# 08-DIPSwitches_I2C.net
KiCad netlist of a schematic drawn in Altium Designer
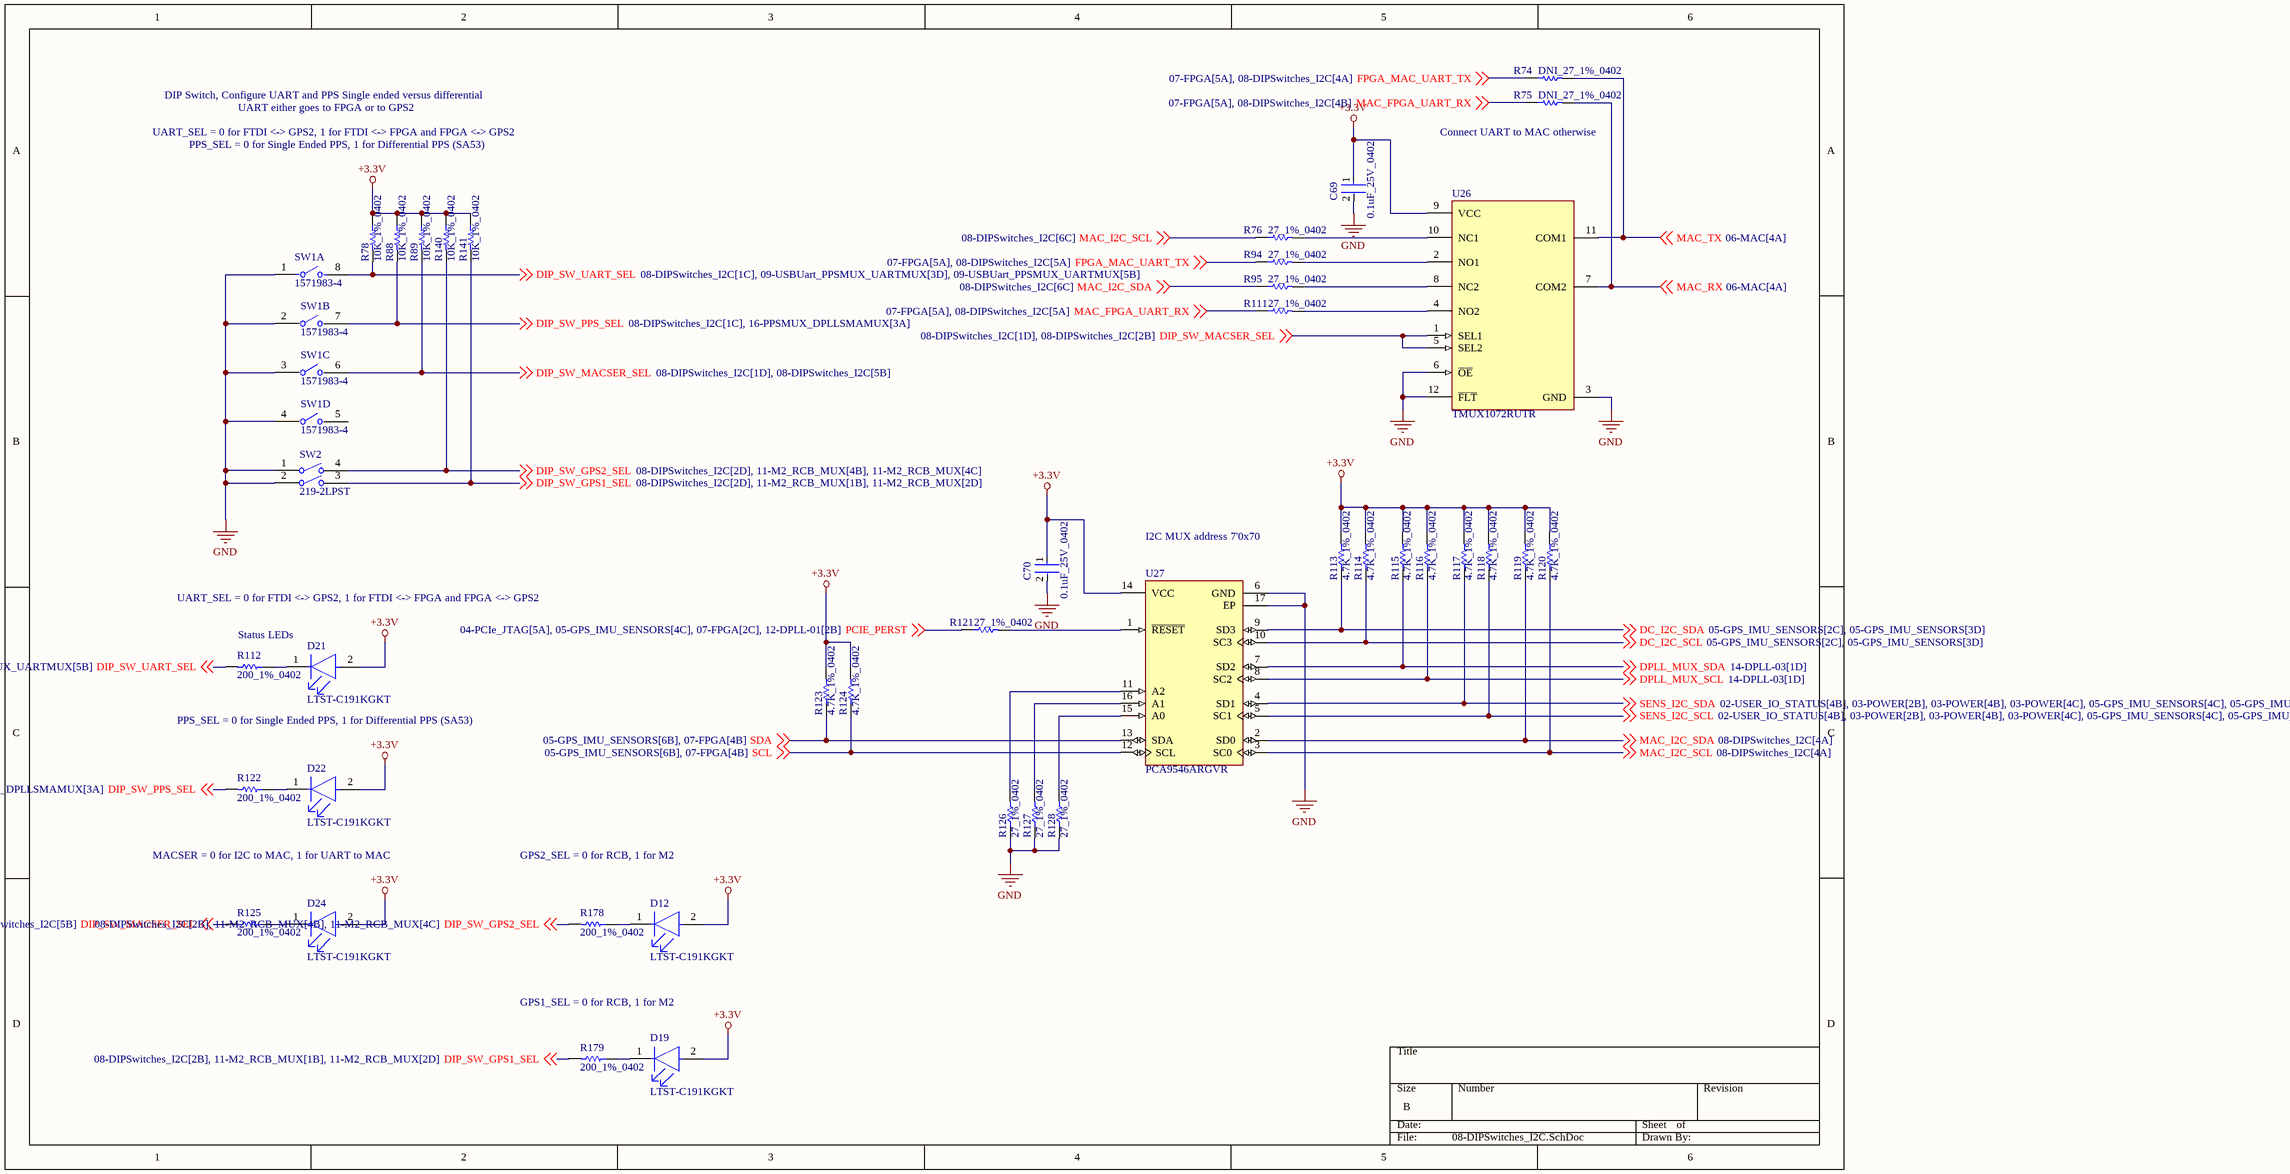
[diagram p0: 08-DIPSwitches_I2C.SchDoc]

(export (version "E")
  (design (tool "Eeschema 10.0.6"))
  (components
    (comp (ref "C69")
      (value "0.1uF_25V_0402")
      (footprint "FP-0402-L_1_0_1-W_0_5_0_1-IPC_C")
      (description "General Purpose Ceramic Capacitor, 0402, 100nF, 10%, X7R, 15%, 25V")
      (fields (field (name "VOLTAGE") "25V") (field (name "TOLERANCE") "10%"))
      (libsource (lib "Altium Content Vault") (part "b4654b650e69147ec39a6b967a45e02"))
    )
    (comp (ref "C70")
      (value "0.1uF_25V_0402")
      (footprint "FP-0402-L_1_0_1-W_0_5_0_1-IPC_C")
      (description "General Purpose Ceramic Capacitor, 0402, 100nF, 10%, X7R, 15%, 25V")
      (fields (field (name "VOLTAGE") "25V") (field (name "TOLERANCE") "10%"))
      (libsource (lib "Altium Content Vault") (part "b4654b650e69147ec39a6b967a45e02"))
    )
    (comp (ref "D12")
      (value "LTST-C191KGKT")
      (footprint "FP-LTST-C191KGKT-MFG")
      (description "LED GREEN CLEAR SMD")
      (libsource (lib "Altium Content Vault") (part "8706943c75ba83719d021d2fdc84c58"))
    )
    (comp (ref "D19")
      (value "LTST-C191KGKT")
      (footprint "FP-LTST-C191KGKT-MFG")
      (description "LED GREEN CLEAR SMD")
      (libsource (lib "Altium Content Vault") (part "8706943c75ba83719d021d2fdc84c58"))
    )
    (comp (ref "D21")
      (value "LTST-C191KGKT")
      (footprint "FP-LTST-C191KGKT-MFG")
      (description "LED GREEN CLEAR SMD")
      (libsource (lib "Altium Content Vault") (part "8706943c75ba83719d021d2fdc84c58"))
    )
    (comp (ref "D22")
      (value "LTST-C191KGKT")
      (footprint "FP-LTST-C191KGKT-MFG")
      (description "LED GREEN CLEAR SMD")
      (libsource (lib "Altium Content Vault") (part "8706943c75ba83719d021d2fdc84c58"))
    )
    (comp (ref "D24")
      (value "LTST-C191KGKT")
      (footprint "FP-LTST-C191KGKT-MFG")
      (description "LED GREEN CLEAR SMD")
      (libsource (lib "Altium Content Vault") (part "8706943c75ba83719d021d2fdc84c58"))
    )
    (comp (ref "R74")
      (value "DNI_27_1%_0402")
      (footprint "RESC1005X40X25NL05T05")
      (fields (field (name "PART NUMBER") "CRCW040227R0FKED") (field (name "MANUFACTURER") "Vishay Dale"))
      (libsource (lib "Altium Content Vault") (part "RES"))
    )
    (comp (ref "R75")
      (value "DNI_27_1%_0402")
      (footprint "RESC1005X40X25NL05T05")
      (fields (field (name "PART NUMBER") "CRCW040227R0FKED") (field (name "MANUFACTURER") "Vishay Dale"))
      (libsource (lib "Altium Content Vault") (part "RES"))
    )
    (comp (ref "R76")
      (value "27_1%_0402")
      (footprint "RESC1005X40X25NL05T05")
      (fields (field (name "PART NUMBER") "CRCW040227R0FKED") (field (name "MANUFACTURER") "Vishay Dale"))
      (libsource (lib "Altium Content Vault") (part "RES"))
    )
    (comp (ref "R78")
      (value "10K_1%_0402")
      (footprint "RESC1005X40X25LL05T10")
      (fields (field (name "PART NUMBER") "RC0402FR-0710KL") (field (name "MANUFACTURER") "Yageo / Phycomp"))
      (libsource (lib "Altium Content Vault") (part "RES"))
    )
    (comp (ref "R88")
      (value "10K_1%_0402")
      (footprint "RESC1005X40X25LL05T10")
      (fields (field (name "PART NUMBER") "RC0402FR-0710KL") (field (name "MANUFACTURER") "Yageo / Phycomp"))
      (libsource (lib "Altium Content Vault") (part "RES"))
    )
    (comp (ref "R89")
      (value "10K_1%_0402")
      (footprint "RESC1005X40X25LL05T10")
      (fields (field (name "PART NUMBER") "RC0402FR-0710KL") (field (name "MANUFACTURER") "Yageo / Phycomp"))
      (libsource (lib "Altium Content Vault") (part "RES"))
    )
    (comp (ref "R94")
      (value "27_1%_0402")
      (footprint "RESC1005X40X25NL05T05")
      (fields (field (name "PART NUMBER") "CRCW040227R0FKED") (field (name "MANUFACTURER") "Vishay Dale"))
      (libsource (lib "Altium Content Vault") (part "RES"))
    )
    (comp (ref "R95")
      (value "27_1%_0402")
      (footprint "RESC1005X40X25NL05T05")
      (fields (field (name "PART NUMBER") "CRCW040227R0FKED") (field (name "MANUFACTURER") "Vishay Dale"))
      (libsource (lib "Altium Content Vault") (part "RES"))
    )
    (comp (ref "R111")
      (value "27_1%_0402")
      (footprint "RESC1005X40X25NL05T05")
      (fields (field (name "PART NUMBER") "CRCW040227R0FKED") (field (name "MANUFACTURER") "Vishay Dale"))
      (libsource (lib "Altium Content Vault") (part "RES"))
    )
    (comp (ref "R112")
      (value "200_1%_0402")
      (footprint "RESC1005X40X25NL05T05")
      (fields (field (name "MANUFACTURER") "Vishay Dale") (field (name "PART NUMBER") "CRCW0402200RFKTD"))
      (libsource (lib "Altium Content Vault") (part "RES"))
    )
    (comp (ref "R113")
      (value "4.7K_1%_0402")
      (footprint "RESC1005X40X25NL10T10")
      (fields (field (name "MANUFACTURER") "Bourns") (field (name "PART NUMBER") "CR0402-FX-4701GLF"))
      (libsource (lib "Altium Content Vault") (part "RES"))
    )
    (comp (ref "R114")
      (value "4.7K_1%_0402")
      (footprint "RESC1005X40X25NL10T10")
      (fields (field (name "MANUFACTURER") "Bourns") (field (name "PART NUMBER") "CR0402-FX-4701GLF"))
      (libsource (lib "Altium Content Vault") (part "RES"))
    )
    (comp (ref "R115")
      (value "4.7K_1%_0402")
      (footprint "RESC1005X40X25NL10T10")
      (fields (field (name "MANUFACTURER") "Bourns") (field (name "PART NUMBER") "CR0402-FX-4701GLF"))
      (libsource (lib "Altium Content Vault") (part "RES"))
    )
    (comp (ref "R116")
      (value "4.7K_1%_0402")
      (footprint "RESC1005X40X25NL10T10")
      (fields (field (name "MANUFACTURER") "Bourns") (field (name "PART NUMBER") "CR0402-FX-4701GLF"))
      (libsource (lib "Altium Content Vault") (part "RES"))
    )
    (comp (ref "R117")
      (value "4.7K_1%_0402")
      (footprint "RESC1005X40X25NL10T10")
      (fields (field (name "MANUFACTURER") "Bourns") (field (name "PART NUMBER") "CR0402-FX-4701GLF"))
      (libsource (lib "Altium Content Vault") (part "RES"))
    )
    (comp (ref "R118")
      (value "4.7K_1%_0402")
      (footprint "RESC1005X40X25NL10T10")
      (fields (field (name "MANUFACTURER") "Bourns") (field (name "PART NUMBER") "CR0402-FX-4701GLF"))
      (libsource (lib "Altium Content Vault") (part "RES"))
    )
    (comp (ref "R119")
      (value "4.7K_1%_0402")
      (footprint "RESC1005X40X25NL10T10")
      (fields (field (name "MANUFACTURER") "Bourns") (field (name "PART NUMBER") "CR0402-FX-4701GLF"))
      (libsource (lib "Altium Content Vault") (part "RES"))
    )
    (comp (ref "R120")
      (value "4.7K_1%_0402")
      (footprint "RESC1005X40X25NL10T10")
      (fields (field (name "MANUFACTURER") "Bourns") (field (name "PART NUMBER") "CR0402-FX-4701GLF"))
      (libsource (lib "Altium Content Vault") (part "RES"))
    )
    (comp (ref "R121")
      (value "27_1%_0402")
      (footprint "RESC1005X40X25NL05T05")
      (fields (field (name "PART NUMBER") "CRCW040227R0FKED") (field (name "MANUFACTURER") "Vishay Dale"))
      (libsource (lib "Altium Content Vault") (part "RES"))
    )
    (comp (ref "R122")
      (value "200_1%_0402")
      (footprint "RESC1005X40X25NL05T05")
      (fields (field (name "MANUFACTURER") "Vishay Dale") (field (name "PART NUMBER") "CRCW0402200RFKTD"))
      (libsource (lib "Altium Content Vault") (part "RES"))
    )
    (comp (ref "R123")
      (value "4.7K_1%_0402")
      (footprint "RESC1005X40X25NL10T10")
      (fields (field (name "MANUFACTURER") "Bourns") (field (name "PART NUMBER") "CR0402-FX-4701GLF"))
      (libsource (lib "Altium Content Vault") (part "RES"))
    )
    (comp (ref "R124")
      (value "4.7K_1%_0402")
      (footprint "RESC1005X40X25NL10T10")
      (fields (field (name "MANUFACTURER") "Bourns") (field (name "PART NUMBER") "CR0402-FX-4701GLF"))
      (libsource (lib "Altium Content Vault") (part "RES"))
    )
    (comp (ref "R125")
      (value "200_1%_0402")
      (footprint "RESC1005X40X25NL05T05")
      (fields (field (name "MANUFACTURER") "Vishay Dale") (field (name "PART NUMBER") "CRCW0402200RFKTD"))
      (libsource (lib "Altium Content Vault") (part "RES"))
    )
    (comp (ref "R126")
      (value "27_1%_0402")
      (footprint "RESC1005X40X25NL05T05")
      (fields (field (name "PART NUMBER") "CRCW040227R0FKED") (field (name "MANUFACTURER") "Vishay Dale"))
      (libsource (lib "Altium Content Vault") (part "RES"))
    )
    (comp (ref "R127")
      (value "27_1%_0402")
      (footprint "RESC1005X40X25NL05T05")
      (fields (field (name "PART NUMBER") "CRCW040227R0FKED") (field (name "MANUFACTURER") "Vishay Dale"))
      (libsource (lib "Altium Content Vault") (part "RES"))
    )
    (comp (ref "R128")
      (value "27_1%_0402")
      (footprint "RESC1005X40X25NL05T05")
      (fields (field (name "PART NUMBER") "CRCW040227R0FKED") (field (name "MANUFACTURER") "Vishay Dale"))
      (libsource (lib "Altium Content Vault") (part "RES"))
    )
    (comp (ref "R140")
      (value "10K_1%_0402")
      (footprint "RESC1005X40X25LL05T10")
      (fields (field (name "PART NUMBER") "RC0402FR-0710KL") (field (name "MANUFACTURER") "Yageo / Phycomp"))
      (libsource (lib "Altium Content Vault") (part "RES"))
    )
    (comp (ref "R141")
      (value "10K_1%_0402")
      (footprint "RESC1005X40X25LL05T10")
      (fields (field (name "PART NUMBER") "RC0402FR-0710KL") (field (name "MANUFACTURER") "Yageo / Phycomp"))
      (libsource (lib "Altium Content Vault") (part "RES"))
    )
    (comp (ref "R178")
      (value "200_1%_0402")
      (footprint "RESC1005X40X25NL05T05")
      (fields (field (name "MANUFACTURER") "Vishay Dale") (field (name "PART NUMBER") "CRCW0402200RFKTD"))
      (libsource (lib "Altium Content Vault") (part "RES"))
    )
    (comp (ref "R179")
      (value "200_1%_0402")
      (footprint "RESC1005X40X25NL05T05")
      (fields (field (name "MANUFACTURER") "Vishay Dale") (field (name "PART NUMBER") "CRCW0402200RFKTD"))
      (libsource (lib "Altium Content Vault") (part "RES"))
    )
    (comp (ref "SW1")
      (value "1571983-4")
      (footprint "FP-1571983-4-MFG")
      (description "SWITCH SLIDE DIP SPST 25MA 24V")
      (fields
        (field (name "OCTOPART") "https://octopart.com/1571983-4-te+connectivity-46507521")
        (field (name "MANUFACTURER") "TE Connectivity")
      )
      (libsource (lib "Altium Content Vault") (part "6123b3bffd52fd60b6df23d79e332fa"))
    )
    (comp (ref "SW2")
      (value "219-2LPST")
      (footprint "CTS-219-2LPST_V")
      (description "Surface Mount DIP Switch Auto Placeable, -55 to 85 degC, 4-Pin SMD, RoHS, Tube")
      (fields (field (name "MANUFACTURER") "CTS Corporation"))
      (libsource (lib "Altium Content Vault") (part "SW-SPST-4_C"))
    )
    (comp (ref "U26")
      (value "TMUX1072RUTR")
      (footprint "FP-RUT0012A-MFG")
      (description "IC SWITCH SPDT DUAL 12UQFN")
      (libsource (lib "Altium Content Vault") (part "12a319ab100cd6cfe745e35972674f5"))
    )
    (comp (ref "U27")
      (value "PCA9546ARGVR")
      (footprint "RGV0016A_V")
      (fields (field (name "MANUFACTURER") "Texas Instruments"))
      (libsource (lib "Altium Content Vault") (part "TI-PCA9546A-VQFN_RGV-16"))
    )
  )
  (nets
    (net (code "1") (name "+3.3V") (class "Default")
      (node (ref "C69") (pin "1") (pinfunction "1_1") (pintype "passive"))
      (node (ref "C70") (pin "1") (pinfunction "1_1") (pintype "passive"))
      (node (ref "D12") (pin "2") (pinfunction "A_2") (pintype "passive"))
      (node (ref "D19") (pin "2") (pinfunction "A_2") (pintype "passive"))
      (node (ref "D21") (pin "2") (pinfunction "A_2") (pintype "passive"))
      (node (ref "D22") (pin "2") (pinfunction "A_2") (pintype "passive"))
      (node (ref "D24") (pin "2") (pinfunction "A_2") (pintype "passive"))
      (node (ref "R113") (pin "2") (pinfunction "2_2") (pintype "passive"))
      (node (ref "R114") (pin "2") (pinfunction "2_2") (pintype "passive"))
      (node (ref "R115") (pin "2") (pinfunction "2_2") (pintype "passive"))
      (node (ref "R116") (pin "2") (pinfunction "2_2") (pintype "passive"))
      (node (ref "R117") (pin "2") (pinfunction "2_2") (pintype "passive"))
      (node (ref "R118") (pin "2") (pinfunction "2_2") (pintype "passive"))
      (node (ref "R119") (pin "2") (pinfunction "2_2") (pintype "passive"))
      (node (ref "R120") (pin "2") (pinfunction "2_2") (pintype "passive"))
      (node (ref "R123") (pin "2") (pinfunction "2_2") (pintype "passive"))
      (node (ref "R124") (pin "2") (pinfunction "2_2") (pintype "passive"))
      (node (ref "R140") (pin "1") (pinfunction "1_1") (pintype "passive"))
      (node (ref "R141") (pin "1") (pinfunction "1_1") (pintype "passive"))
      (node (ref "R78") (pin "1") (pinfunction "1_1") (pintype "passive"))
      (node (ref "R88") (pin "1") (pinfunction "1_1") (pintype "passive"))
      (node (ref "R89") (pin "1") (pinfunction "1_1") (pintype "passive"))
      (node (ref "U26") (pin "9") (pinfunction "VCC_9") (pintype "power_in"))
      (node (ref "U27") (pin "14") (pinfunction "VCC_14") (pintype "power_in"))
    )
    (net (code "2") (name "DC_I2C_SCL") (class "Default")
      (node (ref "R114") (pin "1") (pinfunction "1_1") (pintype "passive"))
      (node (ref "U27") (pin "10") (pinfunction "SC3_10") (pintype "bidirectional"))
    )
    (net (code "3") (name "DC_I2C_SDA") (class "Default")
      (node (ref "R113") (pin "1") (pinfunction "1_1") (pintype "passive"))
      (node (ref "U27") (pin "9") (pinfunction "SD3_9") (pintype "bidirectional"))
    )
    (net (code "4") (name "DIP_SW_GPS1_SEL") (class "Default")
      (node (ref "R141") (pin "2") (pinfunction "2_2") (pintype "passive"))
      (node (ref "R179") (pin "2") (pinfunction "2_2") (pintype "passive"))
      (node (ref "SW2") (pin "3") (pinfunction "3_3") (pintype "passive"))
    )
    (net (code "5") (name "DIP_SW_GPS2_SEL") (class "Default")
      (node (ref "R140") (pin "2") (pinfunction "2_2") (pintype "passive"))
      (node (ref "R178") (pin "2") (pinfunction "2_2") (pintype "passive"))
      (node (ref "SW2") (pin "4") (pinfunction "4_4") (pintype "passive"))
    )
    (net (code "6") (name "DIP_SW_MACSER_SEL") (class "Default")
      (node (ref "R125") (pin "2") (pinfunction "2_2") (pintype "passive"))
      (node (ref "R89") (pin "2") (pinfunction "2_2") (pintype "passive"))
      (node (ref "SW1") (pin "6") (pinfunction "6_6") (pintype "passive"))
      (node (ref "U26") (pin "1") (pinfunction "SEL1_1") (pintype "input"))
      (node (ref "U26") (pin "5") (pinfunction "SEL2_5") (pintype "input"))
    )
    (net (code "7") (name "DIP_SW_PPS_SEL") (class "Default")
      (node (ref "R122") (pin "2") (pinfunction "2_2") (pintype "passive"))
      (node (ref "R88") (pin "2") (pinfunction "2_2") (pintype "passive"))
      (node (ref "SW1") (pin "7") (pinfunction "7_7") (pintype "passive"))
    )
    (net (code "8") (name "DIP_SW_UART_SEL") (class "Default")
      (node (ref "R112") (pin "2") (pinfunction "2_2") (pintype "passive"))
      (node (ref "R78") (pin "2") (pinfunction "2_2") (pintype "passive"))
      (node (ref "SW1") (pin "8") (pinfunction "8_8") (pintype "passive"))
    )
    (net (code "9") (name "DPLL_MUX_SCL") (class "Default")
      (node (ref "R116") (pin "1") (pinfunction "1_1") (pintype "passive"))
      (node (ref "U27") (pin "8") (pinfunction "SC2_8") (pintype "bidirectional"))
    )
    (net (code "10") (name "DPLL_MUX_SDA") (class "Default")
      (node (ref "R115") (pin "1") (pinfunction "1_1") (pintype "passive"))
      (node (ref "U27") (pin "7") (pinfunction "SD2_7") (pintype "bidirectional"))
    )
    (net (code "11") (name "FPGA_MAC_UART_TX") (class "Default")
      (node (ref "R74") (pin "1") (pinfunction "1_1") (pintype "passive"))
      (node (ref "R94") (pin "1") (pinfunction "1_1") (pintype "passive"))
    )
    (net (code "12") (name "GND") (class "Default")
      (node (ref "C69") (pin "2") (pinfunction "2_2") (pintype "passive"))
      (node (ref "C70") (pin "2") (pinfunction "2_2") (pintype "passive"))
      (node (ref "R126") (pin "1") (pinfunction "1_1") (pintype "passive"))
      (node (ref "R127") (pin "1") (pinfunction "1_1") (pintype "passive"))
      (node (ref "R128") (pin "1") (pinfunction "1_1") (pintype "passive"))
      (node (ref "SW1") (pin "1") (pinfunction "1_1") (pintype "passive"))
      (node (ref "SW1") (pin "2") (pinfunction "2_2") (pintype "passive"))
      (node (ref "SW1") (pin "3") (pinfunction "3_3") (pintype "passive"))
      (node (ref "SW1") (pin "4") (pinfunction "4_4") (pintype "passive"))
      (node (ref "SW2") (pin "1") (pinfunction "1_1") (pintype "passive"))
      (node (ref "SW2") (pin "2") (pinfunction "2_2") (pintype "passive"))
      (node (ref "U26") (pin "12") (pinfunction "~{FLT}_12") (pintype "open_collector"))
      (node (ref "U26") (pin "3") (pinfunction "GND_3") (pintype "power_in"))
      (node (ref "U26") (pin "6") (pinfunction "~{OE}_6") (pintype "input"))
      (node (ref "U27") (pin "17") (pinfunction "EP_17") (pintype "passive"))
      (node (ref "U27") (pin "6") (pinfunction "GND_6") (pintype "power_in"))
    )
    (net (code "13") (name "MAC_FPGA_UART_RX") (class "Default")
      (node (ref "R111") (pin "1") (pinfunction "1_1") (pintype "passive"))
      (node (ref "R75") (pin "1") (pinfunction "1_1") (pintype "passive"))
    )
    (net (code "14") (name "MAC_I2C_SCL") (class "Default")
      (node (ref "R120") (pin "1") (pinfunction "1_1") (pintype "passive"))
      (node (ref "R76") (pin "1") (pinfunction "1_1") (pintype "passive"))
      (node (ref "U27") (pin "3") (pinfunction "SC0_3") (pintype "bidirectional"))
    )
    (net (code "15") (name "MAC_I2C_SDA") (class "Default")
      (node (ref "R119") (pin "1") (pinfunction "1_1") (pintype "passive"))
      (node (ref "R95") (pin "1") (pinfunction "1_1") (pintype "passive"))
      (node (ref "U27") (pin "2") (pinfunction "SD0_2") (pintype "bidirectional"))
    )
    (net (code "16") (name "MAC_RX") (class "Default")
      (node (ref "R75") (pin "2") (pinfunction "2_2") (pintype "passive"))
      (node (ref "U26") (pin "7") (pinfunction "COM2_7") (pintype "passive"))
    )
    (net (code "17") (name "MAC_TX") (class "Default")
      (node (ref "R74") (pin "2") (pinfunction "2_2") (pintype "passive"))
      (node (ref "U26") (pin "11") (pinfunction "COM1_11") (pintype "passive"))
    )
    (net (code "18") (name "Net-(D12-C)") (class "Default")
      (node (ref "D12") (pin "1") (pinfunction "C_1") (pintype "passive"))
      (node (ref "R178") (pin "1") (pinfunction "1_1") (pintype "passive"))
    )
    (net (code "19") (name "Net-(D19-C)") (class "Default")
      (node (ref "D19") (pin "1") (pinfunction "C_1") (pintype "passive"))
      (node (ref "R179") (pin "1") (pinfunction "1_1") (pintype "passive"))
    )
    (net (code "20") (name "Net-(D21-C)") (class "Default")
      (node (ref "D21") (pin "1") (pinfunction "C_1") (pintype "passive"))
      (node (ref "R112") (pin "1") (pinfunction "1_1") (pintype "passive"))
    )
    (net (code "21") (name "Net-(D22-C)") (class "Default")
      (node (ref "D22") (pin "1") (pinfunction "C_1") (pintype "passive"))
      (node (ref "R122") (pin "1") (pinfunction "1_1") (pintype "passive"))
    )
    (net (code "22") (name "Net-(D24-C)") (class "Default")
      (node (ref "D24") (pin "1") (pinfunction "C_1") (pintype "passive"))
      (node (ref "R125") (pin "1") (pinfunction "1_1") (pintype "passive"))
    )
    (net (code "23") (name "Net-(U26-NC1)") (class "Default")
      (node (ref "R76") (pin "2") (pinfunction "2_2") (pintype "passive"))
      (node (ref "U26") (pin "10") (pinfunction "NC1_10") (pintype "passive"))
    )
    (net (code "24") (name "Net-(U26-NC2)") (class "Default")
      (node (ref "R95") (pin "2") (pinfunction "2_2") (pintype "passive"))
      (node (ref "U26") (pin "8") (pinfunction "NC2_8") (pintype "passive"))
    )
    (net (code "25") (name "Net-(U26-NO1)") (class "Default")
      (node (ref "R94") (pin "2") (pinfunction "2_2") (pintype "passive"))
      (node (ref "U26") (pin "2") (pinfunction "NO1_2") (pintype "passive"))
    )
    (net (code "26") (name "Net-(U26-NO2)") (class "Default")
      (node (ref "R111") (pin "2") (pinfunction "2_2") (pintype "passive"))
      (node (ref "U26") (pin "4") (pinfunction "NO2_4") (pintype "passive"))
    )
    (net (code "27") (name "Net-(U27-A0)") (class "Default")
      (node (ref "R128") (pin "2") (pinfunction "2_2") (pintype "passive"))
      (node (ref "U27") (pin "15") (pinfunction "A0_15") (pintype "input"))
    )
    (net (code "28") (name "Net-(U27-A1)") (class "Default")
      (node (ref "R127") (pin "2") (pinfunction "2_2") (pintype "passive"))
      (node (ref "U27") (pin "16") (pinfunction "A1_16") (pintype "input"))
    )
    (net (code "29") (name "Net-(U27-A2)") (class "Default")
      (node (ref "R126") (pin "2") (pinfunction "2_2") (pintype "passive"))
      (node (ref "U27") (pin "11") (pinfunction "A2_11") (pintype "input"))
    )
    (net (code "30") (name "Net-(U27-~{RESET})") (class "Default")
      (node (ref "R121") (pin "2") (pinfunction "2_2") (pintype "passive"))
      (node (ref "U27") (pin "1") (pinfunction "~{RESET}_1") (pintype "input"))
    )
    (net (code "31") (name "PCIE_PERST") (class "Default")
      (node (ref "R121") (pin "1") (pinfunction "1_1") (pintype "passive"))
    )
    (net (code "32") (name "SCL") (class "Default")
      (node (ref "R124") (pin "1") (pinfunction "1_1") (pintype "passive"))
      (node (ref "U27") (pin "12") (pinfunction "SCL_12") (pintype "bidirectional"))
    )
    (net (code "33") (name "SDA") (class "Default")
      (node (ref "R123") (pin "1") (pinfunction "1_1") (pintype "passive"))
      (node (ref "U27") (pin "13") (pinfunction "SDA_13") (pintype "bidirectional"))
    )
    (net (code "34") (name "SENS_I2C_SCL") (class "Default")
      (node (ref "R118") (pin "1") (pinfunction "1_1") (pintype "passive"))
      (node (ref "U27") (pin "5") (pinfunction "SC1_5") (pintype "bidirectional"))
    )
    (net (code "35") (name "SENS_I2C_SDA") (class "Default")
      (node (ref "R117") (pin "1") (pinfunction "1_1") (pintype "passive"))
      (node (ref "U27") (pin "4") (pinfunction "SD1_4") (pintype "bidirectional"))
    )
    (net (code "36") (name "unconnected-(SW1-Pad5)") (class "Default")
      (node (ref "SW1") (pin "5") (pinfunction "5_5") (pintype "passive"))
    )
  )
)
